# target_LED_ring_5050.net
KiCad netlist of a schematic drawn in Altium Designer
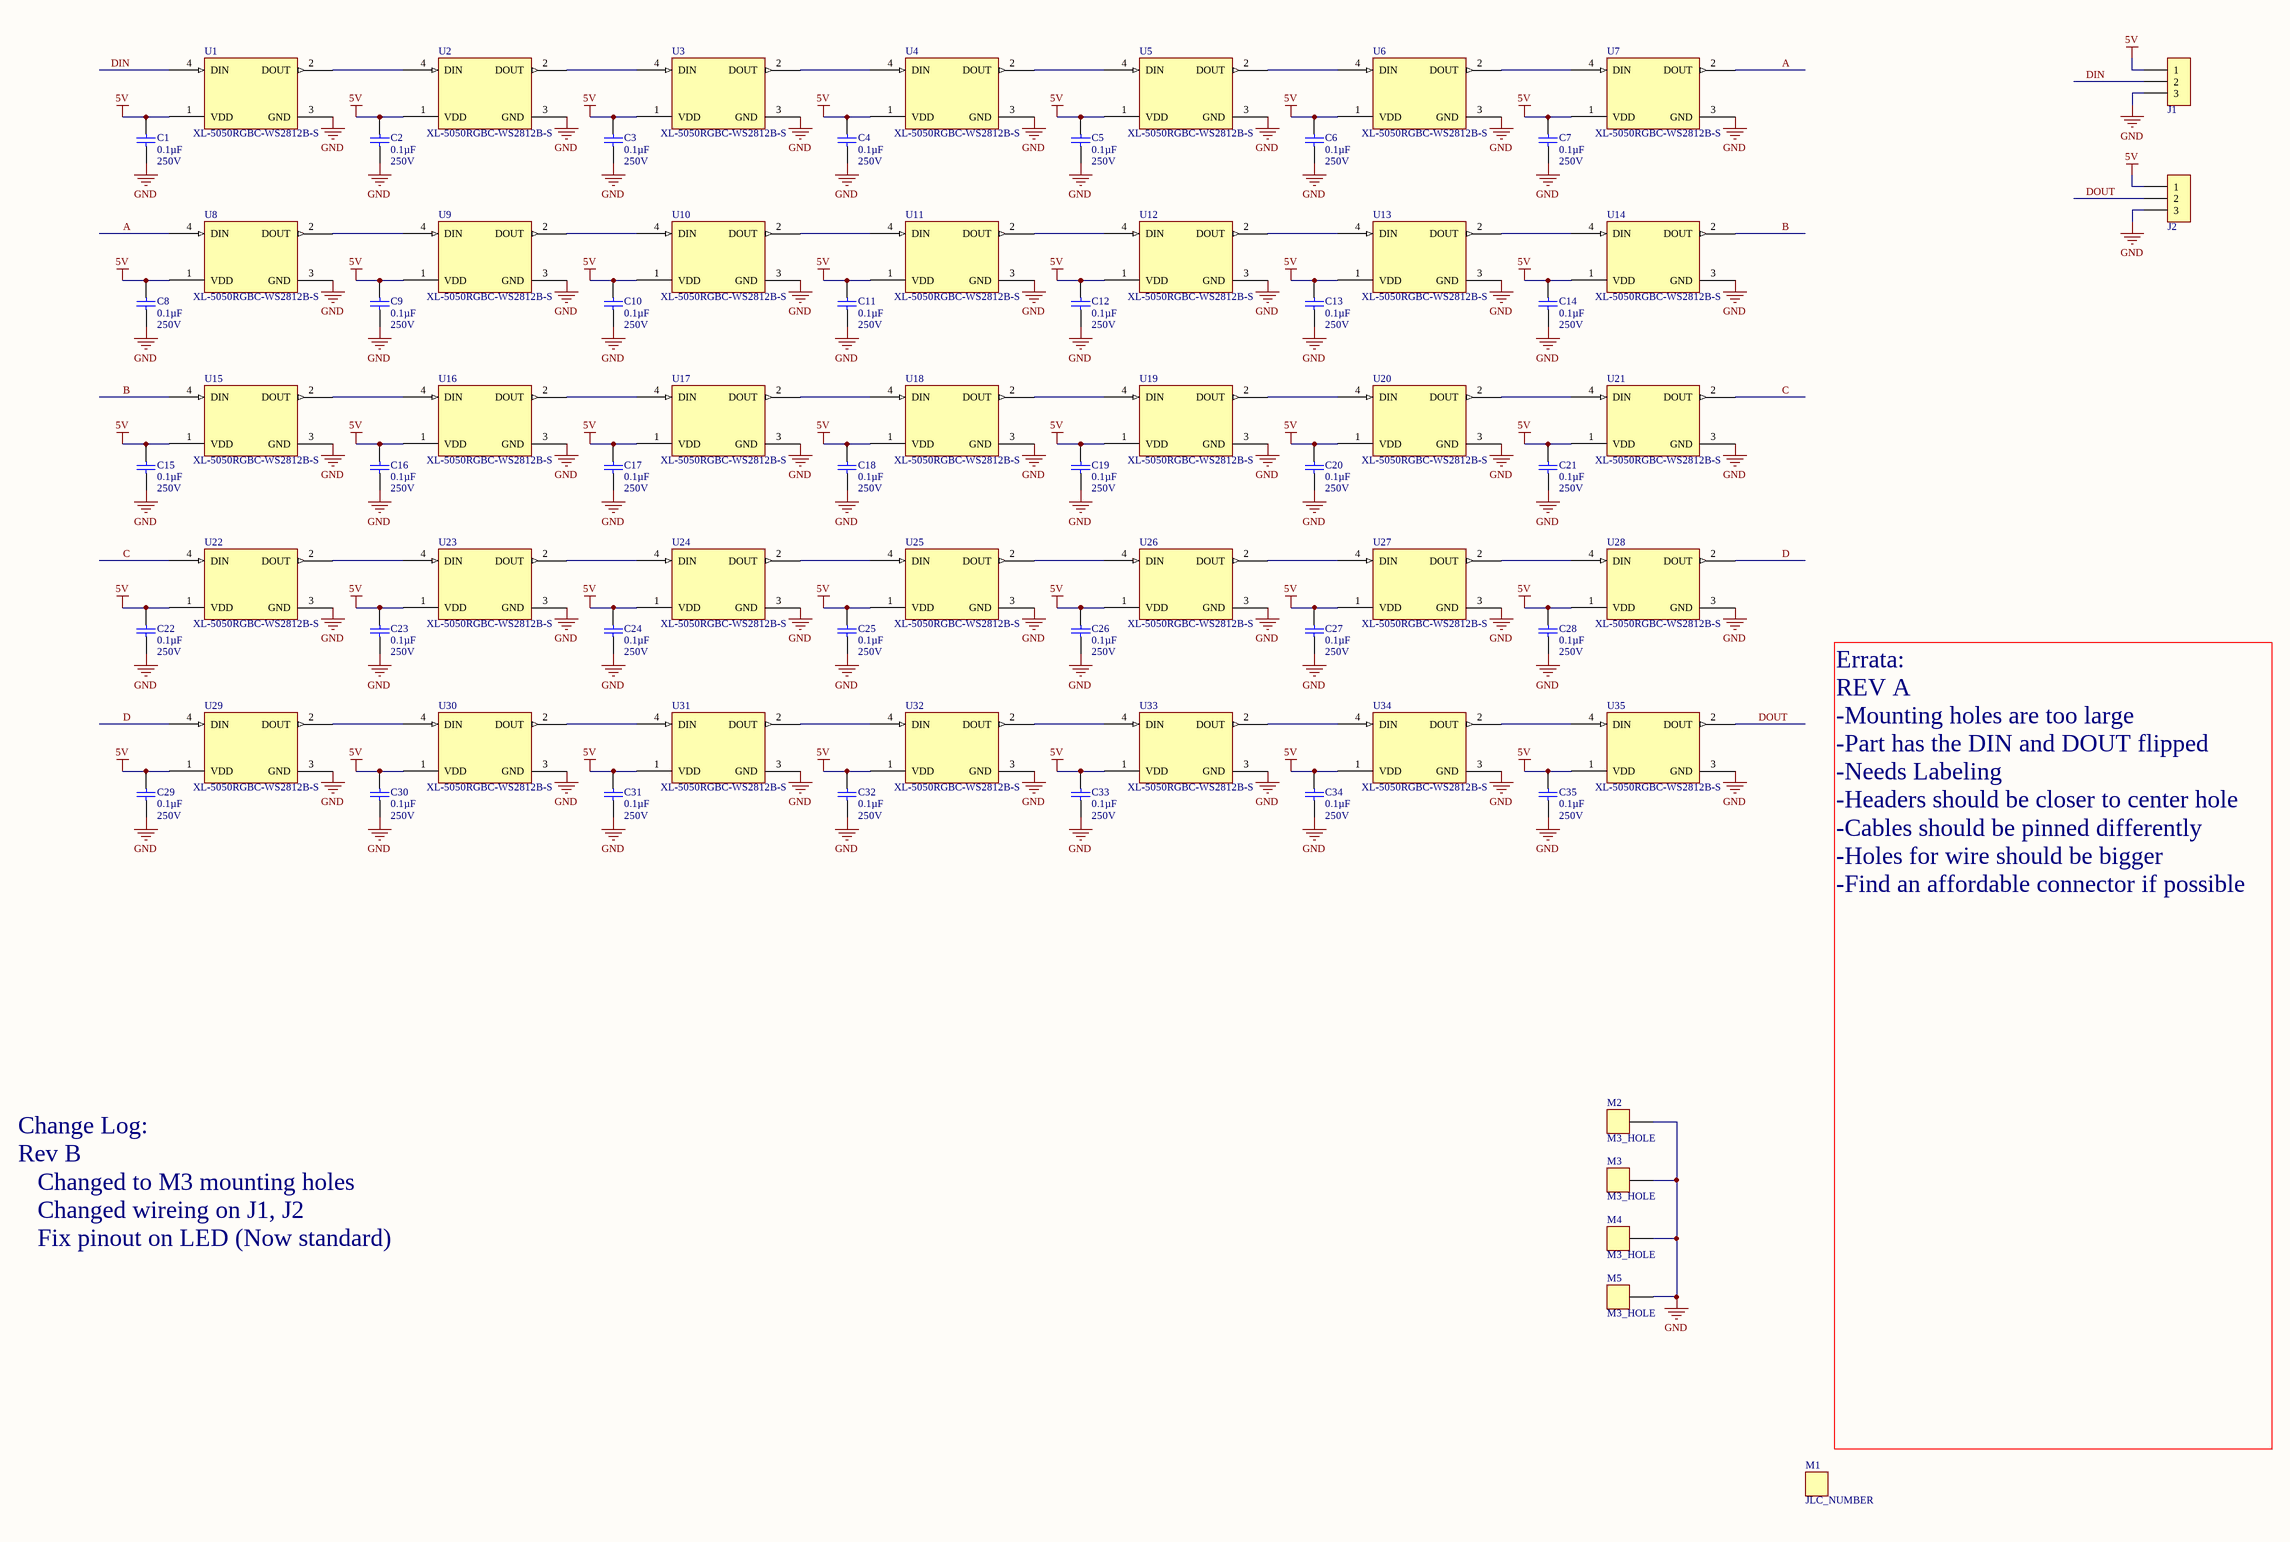
[diagram p0: target_LED_ring_5050.SchDoc]

(export (version "E")
  (design (tool "Eeschema 10.0.6"))
  (components
    (comp (ref "C1")
      (value "0.1µF")
      (footprint "Chip0805")
      (description "CAP CER 0.1UF 250V 10% X7T 0805")
      (fields
        (field (name "VOLTAGE") "250V")
        (field (name "PARTNUMBER") "C2012X7T2E104K125AA")
        (field (name "MANUFACTURER") "TDK Corporation")
      )
      (libsource (lib "Passives") (part "CAP"))
    )
    (comp (ref "C2")
      (value "0.1µF")
      (footprint "Chip0805")
      (description "CAP CER 0.1UF 250V 10% X7T 0805")
      (fields
        (field (name "VOLTAGE") "250V")
        (field (name "PARTNUMBER") "C2012X7T2E104K125AA")
        (field (name "MANUFACTURER") "TDK Corporation")
      )
      (libsource (lib "Passives") (part "CAP"))
    )
    (comp (ref "C3")
      (value "0.1µF")
      (footprint "Chip0805")
      (description "CAP CER 0.1UF 250V 10% X7T 0805")
      (fields
        (field (name "VOLTAGE") "250V")
        (field (name "PARTNUMBER") "C2012X7T2E104K125AA")
        (field (name "MANUFACTURER") "TDK Corporation")
      )
      (libsource (lib "Passives") (part "CAP"))
    )
    (comp (ref "C4")
      (value "0.1µF")
      (footprint "Chip0805")
      (description "CAP CER 0.1UF 250V 10% X7T 0805")
      (fields
        (field (name "VOLTAGE") "250V")
        (field (name "PARTNUMBER") "C2012X7T2E104K125AA")
        (field (name "MANUFACTURER") "TDK Corporation")
      )
      (libsource (lib "Passives") (part "CAP"))
    )
    (comp (ref "C5")
      (value "0.1µF")
      (footprint "Chip0805")
      (description "CAP CER 0.1UF 250V 10% X7T 0805")
      (fields
        (field (name "VOLTAGE") "250V")
        (field (name "PARTNUMBER") "C2012X7T2E104K125AA")
        (field (name "MANUFACTURER") "TDK Corporation")
      )
      (libsource (lib "Passives") (part "CAP"))
    )
    (comp (ref "C6")
      (value "0.1µF")
      (footprint "Chip0805")
      (description "CAP CER 0.1UF 250V 10% X7T 0805")
      (fields
        (field (name "VOLTAGE") "250V")
        (field (name "PARTNUMBER") "C2012X7T2E104K125AA")
        (field (name "MANUFACTURER") "TDK Corporation")
      )
      (libsource (lib "Passives") (part "CAP"))
    )
    (comp (ref "C7")
      (value "0.1µF")
      (footprint "Chip0805")
      (description "CAP CER 0.1UF 250V 10% X7T 0805")
      (fields
        (field (name "VOLTAGE") "250V")
        (field (name "PARTNUMBER") "C2012X7T2E104K125AA")
        (field (name "MANUFACTURER") "TDK Corporation")
      )
      (libsource (lib "Passives") (part "CAP"))
    )
    (comp (ref "C8")
      (value "0.1µF")
      (footprint "Chip0805")
      (description "CAP CER 0.1UF 250V 10% X7T 0805")
      (fields
        (field (name "VOLTAGE") "250V")
        (field (name "PARTNUMBER") "C2012X7T2E104K125AA")
        (field (name "MANUFACTURER") "TDK Corporation")
      )
      (libsource (lib "Passives") (part "CAP"))
    )
    (comp (ref "C9")
      (value "0.1µF")
      (footprint "Chip0805")
      (description "CAP CER 0.1UF 250V 10% X7T 0805")
      (fields
        (field (name "VOLTAGE") "250V")
        (field (name "PARTNUMBER") "C2012X7T2E104K125AA")
        (field (name "MANUFACTURER") "TDK Corporation")
      )
      (libsource (lib "Passives") (part "CAP"))
    )
    (comp (ref "C10")
      (value "0.1µF")
      (footprint "Chip0805")
      (description "CAP CER 0.1UF 250V 10% X7T 0805")
      (fields
        (field (name "VOLTAGE") "250V")
        (field (name "PARTNUMBER") "C2012X7T2E104K125AA")
        (field (name "MANUFACTURER") "TDK Corporation")
      )
      (libsource (lib "Passives") (part "CAP"))
    )
    (comp (ref "C11")
      (value "0.1µF")
      (footprint "Chip0805")
      (description "CAP CER 0.1UF 250V 10% X7T 0805")
      (fields
        (field (name "VOLTAGE") "250V")
        (field (name "PARTNUMBER") "C2012X7T2E104K125AA")
        (field (name "MANUFACTURER") "TDK Corporation")
      )
      (libsource (lib "Passives") (part "CAP"))
    )
    (comp (ref "C12")
      (value "0.1µF")
      (footprint "Chip0805")
      (description "CAP CER 0.1UF 250V 10% X7T 0805")
      (fields
        (field (name "VOLTAGE") "250V")
        (field (name "PARTNUMBER") "C2012X7T2E104K125AA")
        (field (name "MANUFACTURER") "TDK Corporation")
      )
      (libsource (lib "Passives") (part "CAP"))
    )
    (comp (ref "C13")
      (value "0.1µF")
      (footprint "Chip0805")
      (description "CAP CER 0.1UF 250V 10% X7T 0805")
      (fields
        (field (name "VOLTAGE") "250V")
        (field (name "PARTNUMBER") "C2012X7T2E104K125AA")
        (field (name "MANUFACTURER") "TDK Corporation")
      )
      (libsource (lib "Passives") (part "CAP"))
    )
    (comp (ref "C14")
      (value "0.1µF")
      (footprint "Chip0805")
      (description "CAP CER 0.1UF 250V 10% X7T 0805")
      (fields
        (field (name "VOLTAGE") "250V")
        (field (name "PARTNUMBER") "C2012X7T2E104K125AA")
        (field (name "MANUFACTURER") "TDK Corporation")
      )
      (libsource (lib "Passives") (part "CAP"))
    )
    (comp (ref "C15")
      (value "0.1µF")
      (footprint "Chip0805")
      (description "CAP CER 0.1UF 250V 10% X7T 0805")
      (fields
        (field (name "VOLTAGE") "250V")
        (field (name "PARTNUMBER") "C2012X7T2E104K125AA")
        (field (name "MANUFACTURER") "TDK Corporation")
      )
      (libsource (lib "Passives") (part "CAP"))
    )
    (comp (ref "C16")
      (value "0.1µF")
      (footprint "Chip0805")
      (description "CAP CER 0.1UF 250V 10% X7T 0805")
      (fields
        (field (name "VOLTAGE") "250V")
        (field (name "PARTNUMBER") "C2012X7T2E104K125AA")
        (field (name "MANUFACTURER") "TDK Corporation")
      )
      (libsource (lib "Passives") (part "CAP"))
    )
    (comp (ref "C17")
      (value "0.1µF")
      (footprint "Chip0805")
      (description "CAP CER 0.1UF 250V 10% X7T 0805")
      (fields
        (field (name "VOLTAGE") "250V")
        (field (name "PARTNUMBER") "C2012X7T2E104K125AA")
        (field (name "MANUFACTURER") "TDK Corporation")
      )
      (libsource (lib "Passives") (part "CAP"))
    )
    (comp (ref "C18")
      (value "0.1µF")
      (footprint "Chip0805")
      (description "CAP CER 0.1UF 250V 10% X7T 0805")
      (fields
        (field (name "VOLTAGE") "250V")
        (field (name "PARTNUMBER") "C2012X7T2E104K125AA")
        (field (name "MANUFACTURER") "TDK Corporation")
      )
      (libsource (lib "Passives") (part "CAP"))
    )
    (comp (ref "C19")
      (value "0.1µF")
      (footprint "Chip0805")
      (description "CAP CER 0.1UF 250V 10% X7T 0805")
      (fields
        (field (name "VOLTAGE") "250V")
        (field (name "PARTNUMBER") "C2012X7T2E104K125AA")
        (field (name "MANUFACTURER") "TDK Corporation")
      )
      (libsource (lib "Passives") (part "CAP"))
    )
    (comp (ref "C20")
      (value "0.1µF")
      (footprint "Chip0805")
      (description "CAP CER 0.1UF 250V 10% X7T 0805")
      (fields
        (field (name "VOLTAGE") "250V")
        (field (name "PARTNUMBER") "C2012X7T2E104K125AA")
        (field (name "MANUFACTURER") "TDK Corporation")
      )
      (libsource (lib "Passives") (part "CAP"))
    )
    (comp (ref "C21")
      (value "0.1µF")
      (footprint "Chip0805")
      (description "CAP CER 0.1UF 250V 10% X7T 0805")
      (fields
        (field (name "VOLTAGE") "250V")
        (field (name "PARTNUMBER") "C2012X7T2E104K125AA")
        (field (name "MANUFACTURER") "TDK Corporation")
      )
      (libsource (lib "Passives") (part "CAP"))
    )
    (comp (ref "C22")
      (value "0.1µF")
      (footprint "Chip0805")
      (description "CAP CER 0.1UF 250V 10% X7T 0805")
      (fields
        (field (name "VOLTAGE") "250V")
        (field (name "PARTNUMBER") "C2012X7T2E104K125AA")
        (field (name "MANUFACTURER") "TDK Corporation")
      )
      (libsource (lib "Passives") (part "CAP"))
    )
    (comp (ref "C23")
      (value "0.1µF")
      (footprint "Chip0805")
      (description "CAP CER 0.1UF 250V 10% X7T 0805")
      (fields
        (field (name "VOLTAGE") "250V")
        (field (name "PARTNUMBER") "C2012X7T2E104K125AA")
        (field (name "MANUFACTURER") "TDK Corporation")
      )
      (libsource (lib "Passives") (part "CAP"))
    )
    (comp (ref "C24")
      (value "0.1µF")
      (footprint "Chip0805")
      (description "CAP CER 0.1UF 250V 10% X7T 0805")
      (fields
        (field (name "VOLTAGE") "250V")
        (field (name "PARTNUMBER") "C2012X7T2E104K125AA")
        (field (name "MANUFACTURER") "TDK Corporation")
      )
      (libsource (lib "Passives") (part "CAP"))
    )
    (comp (ref "C25")
      (value "0.1µF")
      (footprint "Chip0805")
      (description "CAP CER 0.1UF 250V 10% X7T 0805")
      (fields
        (field (name "VOLTAGE") "250V")
        (field (name "PARTNUMBER") "C2012X7T2E104K125AA")
        (field (name "MANUFACTURER") "TDK Corporation")
      )
      (libsource (lib "Passives") (part "CAP"))
    )
    (comp (ref "C26")
      (value "0.1µF")
      (footprint "Chip0805")
      (description "CAP CER 0.1UF 250V 10% X7T 0805")
      (fields
        (field (name "VOLTAGE") "250V")
        (field (name "PARTNUMBER") "C2012X7T2E104K125AA")
        (field (name "MANUFACTURER") "TDK Corporation")
      )
      (libsource (lib "Passives") (part "CAP"))
    )
    (comp (ref "C27")
      (value "0.1µF")
      (footprint "Chip0805")
      (description "CAP CER 0.1UF 250V 10% X7T 0805")
      (fields
        (field (name "VOLTAGE") "250V")
        (field (name "PARTNUMBER") "C2012X7T2E104K125AA")
        (field (name "MANUFACTURER") "TDK Corporation")
      )
      (libsource (lib "Passives") (part "CAP"))
    )
    (comp (ref "C28")
      (value "0.1µF")
      (footprint "Chip0805")
      (description "CAP CER 0.1UF 250V 10% X7T 0805")
      (fields
        (field (name "VOLTAGE") "250V")
        (field (name "PARTNUMBER") "C2012X7T2E104K125AA")
        (field (name "MANUFACTURER") "TDK Corporation")
      )
      (libsource (lib "Passives") (part "CAP"))
    )
    (comp (ref "C29")
      (value "0.1µF")
      (footprint "Chip0805")
      (description "CAP CER 0.1UF 250V 10% X7T 0805")
      (fields
        (field (name "VOLTAGE") "250V")
        (field (name "PARTNUMBER") "C2012X7T2E104K125AA")
        (field (name "MANUFACTURER") "TDK Corporation")
      )
      (libsource (lib "Passives") (part "CAP"))
    )
    (comp (ref "C30")
      (value "0.1µF")
      (footprint "Chip0805")
      (description "CAP CER 0.1UF 250V 10% X7T 0805")
      (fields
        (field (name "VOLTAGE") "250V")
        (field (name "PARTNUMBER") "C2012X7T2E104K125AA")
        (field (name "MANUFACTURER") "TDK Corporation")
      )
      (libsource (lib "Passives") (part "CAP"))
    )
    (comp (ref "C31")
      (value "0.1µF")
      (footprint "Chip0805")
      (description "CAP CER 0.1UF 250V 10% X7T 0805")
      (fields
        (field (name "VOLTAGE") "250V")
        (field (name "PARTNUMBER") "C2012X7T2E104K125AA")
        (field (name "MANUFACTURER") "TDK Corporation")
      )
      (libsource (lib "Passives") (part "CAP"))
    )
    (comp (ref "C32")
      (value "0.1µF")
      (footprint "Chip0805")
      (description "CAP CER 0.1UF 250V 10% X7T 0805")
      (fields
        (field (name "VOLTAGE") "250V")
        (field (name "PARTNUMBER") "C2012X7T2E104K125AA")
        (field (name "MANUFACTURER") "TDK Corporation")
      )
      (libsource (lib "Passives") (part "CAP"))
    )
    (comp (ref "C33")
      (value "0.1µF")
      (footprint "Chip0805")
      (description "CAP CER 0.1UF 250V 10% X7T 0805")
      (fields
        (field (name "VOLTAGE") "250V")
        (field (name "PARTNUMBER") "C2012X7T2E104K125AA")
        (field (name "MANUFACTURER") "TDK Corporation")
      )
      (libsource (lib "Passives") (part "CAP"))
    )
    (comp (ref "C34")
      (value "0.1µF")
      (footprint "Chip0805")
      (description "CAP CER 0.1UF 250V 10% X7T 0805")
      (fields
        (field (name "VOLTAGE") "250V")
        (field (name "PARTNUMBER") "C2012X7T2E104K125AA")
        (field (name "MANUFACTURER") "TDK Corporation")
      )
      (libsource (lib "Passives") (part "CAP"))
    )
    (comp (ref "C35")
      (value "0.1µF")
      (footprint "Chip0805")
      (description "CAP CER 0.1UF 250V 10% X7T 0805")
      (fields
        (field (name "VOLTAGE") "250V")
        (field (name "PARTNUMBER") "C2012X7T2E104K125AA")
        (field (name "MANUFACTURER") "TDK Corporation")
      )
      (libsource (lib "Passives") (part "CAP"))
    )
    (comp (ref "J1")
      (value "3-644456-3")
      (footprint "TE_3-644456-3")
      (description "CONN HEADER VERT 3POS .100 TIN")
      (fields (field (name "MANUFACTURER") "TE Connectivity"))
      (libsource (lib "Connectors") (part "HEADER_1x3"))
    )
    (comp (ref "J2")
      (value "3-644456-3")
      (footprint "TE_3-644456-3")
      (description "CONN HEADER VERT 3POS .100 TIN")
      (fields (field (name "MANUFACTURER") "TE Connectivity"))
      (libsource (lib "Connectors") (part "HEADER_1x3"))
    )
    (comp (ref "M1")
      (value "JLC_NUMBER")
      (footprint "JLC_NUMBER")
      (description "JLC Order Number Location")
      (libsource (lib "Mechanical") (part "MECH_NO_BOM"))
    )
    (comp (ref "M2")
      (value "M3_HOLE")
      (footprint "M3_HOLE")
      (libsource (lib "Mechanical") (part "MECH_1PIN_NO_BOM"))
    )
    (comp (ref "M3")
      (value "M3_HOLE")
      (footprint "M3_HOLE")
      (libsource (lib "Mechanical") (part "MECH_1PIN_NO_BOM"))
    )
    (comp (ref "M4")
      (value "M3_HOLE")
      (footprint "M3_HOLE")
      (libsource (lib "Mechanical") (part "MECH_1PIN_NO_BOM"))
    )
    (comp (ref "M5")
      (value "M3_HOLE")
      (footprint "M3_HOLE")
      (libsource (lib "Mechanical") (part "MECH_1PIN_NO_BOM"))
    )
    (comp (ref "U1")
      (value "XL-5050RGBC-WS2812B-S")
      (footprint "XINGLIGHT_XL-5050RGBC-WS2812B-S")
      (description "Addressable RGB LED")
      (fields (field (name "MANUFACTURER") "XINGLIGHT"))
      (libsource (lib "Optoelectronics") (part "XINGLIGHT_XL-5050RGBC-WS2812B-S"))
    )
    (comp (ref "U2")
      (value "XL-5050RGBC-WS2812B-S")
      (footprint "XINGLIGHT_XL-5050RGBC-WS2812B-S")
      (description "Addressable RGB LED")
      (fields (field (name "MANUFACTURER") "XINGLIGHT"))
      (libsource (lib "Optoelectronics") (part "XINGLIGHT_XL-5050RGBC-WS2812B-S"))
    )
    (comp (ref "U3")
      (value "XL-5050RGBC-WS2812B-S")
      (footprint "XINGLIGHT_XL-5050RGBC-WS2812B-S")
      (description "Addressable RGB LED")
      (fields (field (name "MANUFACTURER") "XINGLIGHT"))
      (libsource (lib "Optoelectronics") (part "XINGLIGHT_XL-5050RGBC-WS2812B-S"))
    )
    (comp (ref "U4")
      (value "XL-5050RGBC-WS2812B-S")
      (footprint "XINGLIGHT_XL-5050RGBC-WS2812B-S")
      (description "Addressable RGB LED")
      (fields (field (name "MANUFACTURER") "XINGLIGHT"))
      (libsource (lib "Optoelectronics") (part "XINGLIGHT_XL-5050RGBC-WS2812B-S"))
    )
    (comp (ref "U5")
      (value "XL-5050RGBC-WS2812B-S")
      (footprint "XINGLIGHT_XL-5050RGBC-WS2812B-S")
      (description "Addressable RGB LED")
      (fields (field (name "MANUFACTURER") "XINGLIGHT"))
      (libsource (lib "Optoelectronics") (part "XINGLIGHT_XL-5050RGBC-WS2812B-S"))
    )
    (comp (ref "U6")
      (value "XL-5050RGBC-WS2812B-S")
      (footprint "XINGLIGHT_XL-5050RGBC-WS2812B-S")
      (description "Addressable RGB LED")
      (fields (field (name "MANUFACTURER") "XINGLIGHT"))
      (libsource (lib "Optoelectronics") (part "XINGLIGHT_XL-5050RGBC-WS2812B-S"))
    )
    (comp (ref "U7")
      (value "XL-5050RGBC-WS2812B-S")
      (footprint "XINGLIGHT_XL-5050RGBC-WS2812B-S")
      (description "Addressable RGB LED")
      (fields (field (name "MANUFACTURER") "XINGLIGHT"))
      (libsource (lib "Optoelectronics") (part "XINGLIGHT_XL-5050RGBC-WS2812B-S"))
    )
    (comp (ref "U8")
      (value "XL-5050RGBC-WS2812B-S")
      (footprint "XINGLIGHT_XL-5050RGBC-WS2812B-S")
      (description "Addressable RGB LED")
      (fields (field (name "MANUFACTURER") "XINGLIGHT"))
      (libsource (lib "Optoelectronics") (part "XINGLIGHT_XL-5050RGBC-WS2812B-S"))
    )
    (comp (ref "U9")
      (value "XL-5050RGBC-WS2812B-S")
      (footprint "XINGLIGHT_XL-5050RGBC-WS2812B-S")
      (description "Addressable RGB LED")
      (fields (field (name "MANUFACTURER") "XINGLIGHT"))
      (libsource (lib "Optoelectronics") (part "XINGLIGHT_XL-5050RGBC-WS2812B-S"))
    )
    (comp (ref "U10")
      (value "XL-5050RGBC-WS2812B-S")
      (footprint "XINGLIGHT_XL-5050RGBC-WS2812B-S")
      (description "Addressable RGB LED")
      (fields (field (name "MANUFACTURER") "XINGLIGHT"))
      (libsource (lib "Optoelectronics") (part "XINGLIGHT_XL-5050RGBC-WS2812B-S"))
    )
    (comp (ref "U11")
      (value "XL-5050RGBC-WS2812B-S")
      (footprint "XINGLIGHT_XL-5050RGBC-WS2812B-S")
      (description "Addressable RGB LED")
      (fields (field (name "MANUFACTURER") "XINGLIGHT"))
      (libsource (lib "Optoelectronics") (part "XINGLIGHT_XL-5050RGBC-WS2812B-S"))
    )
    (comp (ref "U12")
      (value "XL-5050RGBC-WS2812B-S")
      (footprint "XINGLIGHT_XL-5050RGBC-WS2812B-S")
      (description "Addressable RGB LED")
      (fields (field (name "MANUFACTURER") "XINGLIGHT"))
      (libsource (lib "Optoelectronics") (part "XINGLIGHT_XL-5050RGBC-WS2812B-S"))
    )
    (comp (ref "U13")
      (value "XL-5050RGBC-WS2812B-S")
      (footprint "XINGLIGHT_XL-5050RGBC-WS2812B-S")
      (description "Addressable RGB LED")
      (fields (field (name "MANUFACTURER") "XINGLIGHT"))
      (libsource (lib "Optoelectronics") (part "XINGLIGHT_XL-5050RGBC-WS2812B-S"))
    )
    (comp (ref "U14")
      (value "XL-5050RGBC-WS2812B-S")
      (footprint "XINGLIGHT_XL-5050RGBC-WS2812B-S")
      (description "Addressable RGB LED")
      (fields (field (name "MANUFACTURER") "XINGLIGHT"))
      (libsource (lib "Optoelectronics") (part "XINGLIGHT_XL-5050RGBC-WS2812B-S"))
    )
    (comp (ref "U15")
      (value "XL-5050RGBC-WS2812B-S")
      (footprint "XINGLIGHT_XL-5050RGBC-WS2812B-S")
      (description "Addressable RGB LED")
      (fields (field (name "MANUFACTURER") "XINGLIGHT"))
      (libsource (lib "Optoelectronics") (part "XINGLIGHT_XL-5050RGBC-WS2812B-S"))
    )
    (comp (ref "U16")
      (value "XL-5050RGBC-WS2812B-S")
      (footprint "XINGLIGHT_XL-5050RGBC-WS2812B-S")
      (description "Addressable RGB LED")
      (fields (field (name "MANUFACTURER") "XINGLIGHT"))
      (libsource (lib "Optoelectronics") (part "XINGLIGHT_XL-5050RGBC-WS2812B-S"))
    )
    (comp (ref "U17")
      (value "XL-5050RGBC-WS2812B-S")
      (footprint "XINGLIGHT_XL-5050RGBC-WS2812B-S")
      (description "Addressable RGB LED")
      (fields (field (name "MANUFACTURER") "XINGLIGHT"))
      (libsource (lib "Optoelectronics") (part "XINGLIGHT_XL-5050RGBC-WS2812B-S"))
    )
    (comp (ref "U18")
      (value "XL-5050RGBC-WS2812B-S")
      (footprint "XINGLIGHT_XL-5050RGBC-WS2812B-S")
      (description "Addressable RGB LED")
      (fields (field (name "MANUFACTURER") "XINGLIGHT"))
      (libsource (lib "Optoelectronics") (part "XINGLIGHT_XL-5050RGBC-WS2812B-S"))
    )
    (comp (ref "U19")
      (value "XL-5050RGBC-WS2812B-S")
      (footprint "XINGLIGHT_XL-5050RGBC-WS2812B-S")
      (description "Addressable RGB LED")
      (fields (field (name "MANUFACTURER") "XINGLIGHT"))
      (libsource (lib "Optoelectronics") (part "XINGLIGHT_XL-5050RGBC-WS2812B-S"))
    )
    (comp (ref "U20")
      (value "XL-5050RGBC-WS2812B-S")
      (footprint "XINGLIGHT_XL-5050RGBC-WS2812B-S")
      (description "Addressable RGB LED")
      (fields (field (name "MANUFACTURER") "XINGLIGHT"))
      (libsource (lib "Optoelectronics") (part "XINGLIGHT_XL-5050RGBC-WS2812B-S"))
    )
    (comp (ref "U21")
      (value "XL-5050RGBC-WS2812B-S")
      (footprint "XINGLIGHT_XL-5050RGBC-WS2812B-S")
      (description "Addressable RGB LED")
      (fields (field (name "MANUFACTURER") "XINGLIGHT"))
      (libsource (lib "Optoelectronics") (part "XINGLIGHT_XL-5050RGBC-WS2812B-S"))
    )
    (comp (ref "U22")
      (value "XL-5050RGBC-WS2812B-S")
      (footprint "XINGLIGHT_XL-5050RGBC-WS2812B-S")
      (description "Addressable RGB LED")
      (fields (field (name "MANUFACTURER") "XINGLIGHT"))
      (libsource (lib "Optoelectronics") (part "XINGLIGHT_XL-5050RGBC-WS2812B-S"))
    )
    (comp (ref "U23")
      (value "XL-5050RGBC-WS2812B-S")
      (footprint "XINGLIGHT_XL-5050RGBC-WS2812B-S")
      (description "Addressable RGB LED")
      (fields (field (name "MANUFACTURER") "XINGLIGHT"))
      (libsource (lib "Optoelectronics") (part "XINGLIGHT_XL-5050RGBC-WS2812B-S"))
    )
    (comp (ref "U24")
      (value "XL-5050RGBC-WS2812B-S")
      (footprint "XINGLIGHT_XL-5050RGBC-WS2812B-S")
      (description "Addressable RGB LED")
      (fields (field (name "MANUFACTURER") "XINGLIGHT"))
      (libsource (lib "Optoelectronics") (part "XINGLIGHT_XL-5050RGBC-WS2812B-S"))
    )
    (comp (ref "U25")
      (value "XL-5050RGBC-WS2812B-S")
      (footprint "XINGLIGHT_XL-5050RGBC-WS2812B-S")
      (description "Addressable RGB LED")
      (fields (field (name "MANUFACTURER") "XINGLIGHT"))
      (libsource (lib "Optoelectronics") (part "XINGLIGHT_XL-5050RGBC-WS2812B-S"))
    )
    (comp (ref "U26")
      (value "XL-5050RGBC-WS2812B-S")
      (footprint "XINGLIGHT_XL-5050RGBC-WS2812B-S")
      (description "Addressable RGB LED")
      (fields (field (name "MANUFACTURER") "XINGLIGHT"))
      (libsource (lib "Optoelectronics") (part "XINGLIGHT_XL-5050RGBC-WS2812B-S"))
    )
    (comp (ref "U27")
      (value "XL-5050RGBC-WS2812B-S")
      (footprint "XINGLIGHT_XL-5050RGBC-WS2812B-S")
      (description "Addressable RGB LED")
      (fields (field (name "MANUFACTURER") "XINGLIGHT"))
      (libsource (lib "Optoelectronics") (part "XINGLIGHT_XL-5050RGBC-WS2812B-S"))
    )
    (comp (ref "U28")
      (value "XL-5050RGBC-WS2812B-S")
      (footprint "XINGLIGHT_XL-5050RGBC-WS2812B-S")
      (description "Addressable RGB LED")
      (fields (field (name "MANUFACTURER") "XINGLIGHT"))
      (libsource (lib "Optoelectronics") (part "XINGLIGHT_XL-5050RGBC-WS2812B-S"))
    )
    (comp (ref "U29")
      (value "XL-5050RGBC-WS2812B-S")
      (footprint "XINGLIGHT_XL-5050RGBC-WS2812B-S")
      (description "Addressable RGB LED")
      (fields (field (name "MANUFACTURER") "XINGLIGHT"))
      (libsource (lib "Optoelectronics") (part "XINGLIGHT_XL-5050RGBC-WS2812B-S"))
    )
    (comp (ref "U30")
      (value "XL-5050RGBC-WS2812B-S")
      (footprint "XINGLIGHT_XL-5050RGBC-WS2812B-S")
      (description "Addressable RGB LED")
      (fields (field (name "MANUFACTURER") "XINGLIGHT"))
      (libsource (lib "Optoelectronics") (part "XINGLIGHT_XL-5050RGBC-WS2812B-S"))
    )
    (comp (ref "U31")
      (value "XL-5050RGBC-WS2812B-S")
      (footprint "XINGLIGHT_XL-5050RGBC-WS2812B-S")
      (description "Addressable RGB LED")
      (fields (field (name "MANUFACTURER") "XINGLIGHT"))
      (libsource (lib "Optoelectronics") (part "XINGLIGHT_XL-5050RGBC-WS2812B-S"))
    )
    (comp (ref "U32")
      (value "XL-5050RGBC-WS2812B-S")
      (footprint "XINGLIGHT_XL-5050RGBC-WS2812B-S")
      (description "Addressable RGB LED")
      (fields (field (name "MANUFACTURER") "XINGLIGHT"))
      (libsource (lib "Optoelectronics") (part "XINGLIGHT_XL-5050RGBC-WS2812B-S"))
    )
    (comp (ref "U33")
      (value "XL-5050RGBC-WS2812B-S")
      (footprint "XINGLIGHT_XL-5050RGBC-WS2812B-S")
      (description "Addressable RGB LED")
      (fields (field (name "MANUFACTURER") "XINGLIGHT"))
      (libsource (lib "Optoelectronics") (part "XINGLIGHT_XL-5050RGBC-WS2812B-S"))
    )
    (comp (ref "U34")
      (value "XL-5050RGBC-WS2812B-S")
      (footprint "XINGLIGHT_XL-5050RGBC-WS2812B-S")
      (description "Addressable RGB LED")
      (fields (field (name "MANUFACTURER") "XINGLIGHT"))
      (libsource (lib "Optoelectronics") (part "XINGLIGHT_XL-5050RGBC-WS2812B-S"))
    )
    (comp (ref "U35")
      (value "XL-5050RGBC-WS2812B-S")
      (footprint "XINGLIGHT_XL-5050RGBC-WS2812B-S")
      (description "Addressable RGB LED")
      (fields (field (name "MANUFACTURER") "XINGLIGHT"))
      (libsource (lib "Optoelectronics") (part "XINGLIGHT_XL-5050RGBC-WS2812B-S"))
    )
  )
  (nets
    (net (code "1") (name "/A") (class "Default")
      (node (ref "U7") (pin "2") (pinfunction "DOUT_2") (pintype "output"))
      (node (ref "U8") (pin "4") (pinfunction "DIN_4") (pintype "input"))
    )
    (net (code "2") (name "/B") (class "Default")
      (node (ref "U14") (pin "2") (pinfunction "DOUT_2") (pintype "output"))
      (node (ref "U15") (pin "4") (pinfunction "DIN_4") (pintype "input"))
    )
    (net (code "3") (name "/C") (class "Default")
      (node (ref "U21") (pin "2") (pinfunction "DOUT_2") (pintype "output"))
      (node (ref "U22") (pin "4") (pinfunction "DIN_4") (pintype "input"))
    )
    (net (code "4") (name "/D") (class "Default")
      (node (ref "U28") (pin "2") (pinfunction "DOUT_2") (pintype "output"))
      (node (ref "U29") (pin "4") (pinfunction "DIN_4") (pintype "input"))
    )
    (net (code "5") (name "/DIN") (class "Default")
      (node (ref "J1") (pin "2") (pinfunction "2_2") (pintype "passive"))
      (node (ref "U1") (pin "4") (pinfunction "DIN_4") (pintype "input"))
    )
    (net (code "6") (name "/DOUT") (class "Default")
      (node (ref "J2") (pin "2") (pinfunction "2_2") (pintype "passive"))
      (node (ref "U35") (pin "2") (pinfunction "DOUT_2") (pintype "output"))
    )
    (net (code "7") (name "5V") (class "Default")
      (node (ref "C1") (pin "2") (pinfunction "2_2") (pintype "passive"))
      (node (ref "C10") (pin "2") (pinfunction "2_2") (pintype "passive"))
      (node (ref "C11") (pin "2") (pinfunction "2_2") (pintype "passive"))
      (node (ref "C12") (pin "2") (pinfunction "2_2") (pintype "passive"))
      (node (ref "C13") (pin "2") (pinfunction "2_2") (pintype "passive"))
      (node (ref "C14") (pin "2") (pinfunction "2_2") (pintype "passive"))
      (node (ref "C15") (pin "2") (pinfunction "2_2") (pintype "passive"))
      (node (ref "C16") (pin "2") (pinfunction "2_2") (pintype "passive"))
      (node (ref "C17") (pin "2") (pinfunction "2_2") (pintype "passive"))
      (node (ref "C18") (pin "2") (pinfunction "2_2") (pintype "passive"))
      (node (ref "C19") (pin "2") (pinfunction "2_2") (pintype "passive"))
      (node (ref "C2") (pin "2") (pinfunction "2_2") (pintype "passive"))
      (node (ref "C20") (pin "2") (pinfunction "2_2") (pintype "passive"))
      (node (ref "C21") (pin "2") (pinfunction "2_2") (pintype "passive"))
      (node (ref "C22") (pin "2") (pinfunction "2_2") (pintype "passive"))
      (node (ref "C23") (pin "2") (pinfunction "2_2") (pintype "passive"))
      (node (ref "C24") (pin "2") (pinfunction "2_2") (pintype "passive"))
      (node (ref "C25") (pin "2") (pinfunction "2_2") (pintype "passive"))
      (node (ref "C26") (pin "2") (pinfunction "2_2") (pintype "passive"))
      (node (ref "C27") (pin "2") (pinfunction "2_2") (pintype "passive"))
      (node (ref "C28") (pin "2") (pinfunction "2_2") (pintype "passive"))
      (node (ref "C29") (pin "2") (pinfunction "2_2") (pintype "passive"))
      (node (ref "C3") (pin "2") (pinfunction "2_2") (pintype "passive"))
      (node (ref "C30") (pin "2") (pinfunction "2_2") (pintype "passive"))
      (node (ref "C31") (pin "2") (pinfunction "2_2") (pintype "passive"))
      (node (ref "C32") (pin "2") (pinfunction "2_2") (pintype "passive"))
      (node (ref "C33") (pin "2") (pinfunction "2_2") (pintype "passive"))
      (node (ref "C34") (pin "2") (pinfunction "2_2") (pintype "passive"))
      (node (ref "C35") (pin "2") (pinfunction "2_2") (pintype "passive"))
      (node (ref "C4") (pin "2") (pinfunction "2_2") (pintype "passive"))
      (node (ref "C5") (pin "2") (pinfunction "2_2") (pintype "passive"))
      (node (ref "C6") (pin "2") (pinfunction "2_2") (pintype "passive"))
      (node (ref "C7") (pin "2") (pinfunction "2_2") (pintype "passive"))
      (node (ref "C8") (pin "2") (pinfunction "2_2") (pintype "passive"))
      (node (ref "C9") (pin "2") (pinfunction "2_2") (pintype "passive"))
      (node (ref "J1") (pin "1") (pinfunction "1_1") (pintype "passive"))
      (node (ref "J2") (pin "1") (pinfunction "1_1") (pintype "passive"))
      (node (ref "U1") (pin "1") (pinfunction "VDD_1") (pintype "passive"))
      (node (ref "U10") (pin "1") (pinfunction "VDD_1") (pintype "passive"))
      (node (ref "U11") (pin "1") (pinfunction "VDD_1") (pintype "passive"))
      (node (ref "U12") (pin "1") (pinfunction "VDD_1") (pintype "passive"))
      (node (ref "U13") (pin "1") (pinfunction "VDD_1") (pintype "passive"))
      (node (ref "U14") (pin "1") (pinfunction "VDD_1") (pintype "passive"))
      (node (ref "U15") (pin "1") (pinfunction "VDD_1") (pintype "passive"))
      (node (ref "U16") (pin "1") (pinfunction "VDD_1") (pintype "passive"))
      (node (ref "U17") (pin "1") (pinfunction "VDD_1") (pintype "passive"))
      (node (ref "U18") (pin "1") (pinfunction "VDD_1") (pintype "passive"))
      (node (ref "U19") (pin "1") (pinfunction "VDD_1") (pintype "passive"))
      (node (ref "U2") (pin "1") (pinfunction "VDD_1") (pintype "passive"))
      (node (ref "U20") (pin "1") (pinfunction "VDD_1") (pintype "passive"))
      (node (ref "U21") (pin "1") (pinfunction "VDD_1") (pintype "passive"))
      (node (ref "U22") (pin "1") (pinfunction "VDD_1") (pintype "passive"))
      (node (ref "U23") (pin "1") (pinfunction "VDD_1") (pintype "passive"))
      (node (ref "U24") (pin "1") (pinfunction "VDD_1") (pintype "passive"))
      (node (ref "U25") (pin "1") (pinfunction "VDD_1") (pintype "passive"))
      (node (ref "U26") (pin "1") (pinfunction "VDD_1") (pintype "passive"))
      (node (ref "U27") (pin "1") (pinfunction "VDD_1") (pintype "passive"))
      (node (ref "U28") (pin "1") (pinfunction "VDD_1") (pintype "passive"))
      (node (ref "U29") (pin "1") (pinfunction "VDD_1") (pintype "passive"))
      (node (ref "U3") (pin "1") (pinfunction "VDD_1") (pintype "passive"))
      (node (ref "U30") (pin "1") (pinfunction "VDD_1") (pintype "passive"))
      (node (ref "U31") (pin "1") (pinfunction "VDD_1") (pintype "passive"))
      (node (ref "U32") (pin "1") (pinfunction "VDD_1") (pintype "passive"))
      (node (ref "U33") (pin "1") (pinfunction "VDD_1") (pintype "passive"))
      (node (ref "U34") (pin "1") (pinfunction "VDD_1") (pintype "passive"))
      (node (ref "U35") (pin "1") (pinfunction "VDD_1") (pintype "passive"))
      (node (ref "U4") (pin "1") (pinfunction "VDD_1") (pintype "passive"))
      (node (ref "U5") (pin "1") (pinfunction "VDD_1") (pintype "passive"))
      (node (ref "U6") (pin "1") (pinfunction "VDD_1") (pintype "passive"))
      (node (ref "U7") (pin "1") (pinfunction "VDD_1") (pintype "passive"))
      (node (ref "U8") (pin "1") (pinfunction "VDD_1") (pintype "passive"))
      (node (ref "U9") (pin "1") (pinfunction "VDD_1") (pintype "passive"))
    )
    (net (code "8") (name "GND") (class "Default")
      (node (ref "C1") (pin "1") (pinfunction "1_1") (pintype "passive"))
      (node (ref "C10") (pin "1") (pinfunction "1_1") (pintype "passive"))
      (node (ref "C11") (pin "1") (pinfunction "1_1") (pintype "passive"))
      (node (ref "C12") (pin "1") (pinfunction "1_1") (pintype "passive"))
      (node (ref "C13") (pin "1") (pinfunction "1_1") (pintype "passive"))
      (node (ref "C14") (pin "1") (pinfunction "1_1") (pintype "passive"))
      (node (ref "C15") (pin "1") (pinfunction "1_1") (pintype "passive"))
      (node (ref "C16") (pin "1") (pinfunction "1_1") (pintype "passive"))
      (node (ref "C17") (pin "1") (pinfunction "1_1") (pintype "passive"))
      (node (ref "C18") (pin "1") (pinfunction "1_1") (pintype "passive"))
      (node (ref "C19") (pin "1") (pinfunction "1_1") (pintype "passive"))
      (node (ref "C2") (pin "1") (pinfunction "1_1") (pintype "passive"))
      (node (ref "C20") (pin "1") (pinfunction "1_1") (pintype "passive"))
      (node (ref "C21") (pin "1") (pinfunction "1_1") (pintype "passive"))
      (node (ref "C22") (pin "1") (pinfunction "1_1") (pintype "passive"))
      (node (ref "C23") (pin "1") (pinfunction "1_1") (pintype "passive"))
      (node (ref "C24") (pin "1") (pinfunction "1_1") (pintype "passive"))
      (node (ref "C25") (pin "1") (pinfunction "1_1") (pintype "passive"))
      (node (ref "C26") (pin "1") (pinfunction "1_1") (pintype "passive"))
      (node (ref "C27") (pin "1") (pinfunction "1_1") (pintype "passive"))
      (node (ref "C28") (pin "1") (pinfunction "1_1") (pintype "passive"))
      (node (ref "C29") (pin "1") (pinfunction "1_1") (pintype "passive"))
      (node (ref "C3") (pin "1") (pinfunction "1_1") (pintype "passive"))
      (node (ref "C30") (pin "1") (pinfunction "1_1") (pintype "passive"))
      (node (ref "C31") (pin "1") (pinfunction "1_1") (pintype "passive"))
      (node (ref "C32") (pin "1") (pinfunction "1_1") (pintype "passive"))
      (node (ref "C33") (pin "1") (pinfunction "1_1") (pintype "passive"))
      (node (ref "C34") (pin "1") (pinfunction "1_1") (pintype "passive"))
      (node (ref "C35") (pin "1") (pinfunction "1_1") (pintype "passive"))
      (node (ref "C4") (pin "1") (pinfunction "1_1") (pintype "passive"))
      (node (ref "C5") (pin "1") (pinfunction "1_1") (pintype "passive"))
      (node (ref "C6") (pin "1") (pinfunction "1_1") (pintype "passive"))
      (node (ref "C7") (pin "1") (pinfunction "1_1") (pintype "passive"))
      (node (ref "C8") (pin "1") (pinfunction "1_1") (pintype "passive"))
      (node (ref "C9") (pin "1") (pinfunction "1_1") (pintype "passive"))
      (node (ref "J1") (pin "3") (pinfunction "3_3") (pintype "passive"))
      (node (ref "J2") (pin "3") (pinfunction "3_3") (pintype "passive"))
      (node (ref "M2") (pin "1") (pinfunction "1_1") (pintype "passive"))
      (node (ref "M3") (pin "1") (pinfunction "1_1") (pintype "passive"))
      (node (ref "M4") (pin "1") (pinfunction "1_1") (pintype "passive"))
      (node (ref "M5") (pin "1") (pinfunction "1_1") (pintype "passive"))
      (node (ref "U1") (pin "3") (pinfunction "GND_3") (pintype "passive"))
      (node (ref "U10") (pin "3") (pinfunction "GND_3") (pintype "passive"))
      (node (ref "U11") (pin "3") (pinfunction "GND_3") (pintype "passive"))
      (node (ref "U12") (pin "3") (pinfunction "GND_3") (pintype "passive"))
      (node (ref "U13") (pin "3") (pinfunction "GND_3") (pintype "passive"))
      (node (ref "U14") (pin "3") (pinfunction "GND_3") (pintype "passive"))
      (node (ref "U15") (pin "3") (pinfunction "GND_3") (pintype "passive"))
      (node (ref "U16") (pin "3") (pinfunction "GND_3") (pintype "passive"))
      (node (ref "U17") (pin "3") (pinfunction "GND_3") (pintype "passive"))
      (node (ref "U18") (pin "3") (pinfunction "GND_3") (pintype "passive"))
      (node (ref "U19") (pin "3") (pinfunction "GND_3") (pintype "passive"))
      (node (ref "U2") (pin "3") (pinfunction "GND_3") (pintype "passive"))
      (node (ref "U20") (pin "3") (pinfunction "GND_3") (pintype "passive"))
      (node (ref "U21") (pin "3") (pinfunction "GND_3") (pintype "passive"))
      (node (ref "U22") (pin "3") (pinfunction "GND_3") (pintype "passive"))
      (node (ref "U23") (pin "3") (pinfunction "GND_3") (pintype "passive"))
      (node (ref "U24") (pin "3") (pinfunction "GND_3") (pintype "passive"))
      (node (ref "U25") (pin "3") (pinfunction "GND_3") (pintype "passive"))
      (node (ref "U26") (pin "3") (pinfunction "GND_3") (pintype "passive"))
      (node (ref "U27") (pin "3") (pinfunction "GND_3") (pintype "passive"))
      (node (ref "U28") (pin "3") (pinfunction "GND_3") (pintype "passive"))
      (node (ref "U29") (pin "3") (pinfunction "GND_3") (pintype "passive"))
      (node (ref "U3") (pin "3") (pinfunction "GND_3") (pintype "passive"))
      (node (ref "U30") (pin "3") (pinfunction "GND_3") (pintype "passive"))
      (node (ref "U31") (pin "3") (pinfunction "GND_3") (pintype "passive"))
      (node (ref "U32") (pin "3") (pinfunction "GND_3") (pintype "passive"))
      (node (ref "U33") (pin "3") (pinfunction "GND_3") (pintype "passive"))
      (node (ref "U34") (pin "3") (pinfunction "GND_3") (pintype "passive"))
      (node (ref "U35") (pin "3") (pinfunction "GND_3") (pintype "passive"))
      (node (ref "U4") (pin "3") (pinfunction "GND_3") (pintype "passive"))
      (node (ref "U5") (pin "3") (pinfunction "GND_3") (pintype "passive"))
      (node (ref "U6") (pin "3") (pinfunction "GND_3") (pintype "passive"))
      (node (ref "U7") (pin "3") (pinfunction "GND_3") (pintype "passive"))
      (node (ref "U8") (pin "3") (pinfunction "GND_3") (pintype "passive"))
      (node (ref "U9") (pin "3") (pinfunction "GND_3") (pintype "passive"))
    )
    (net (code "9") (name "Net-(U1-DOUT)") (class "Default")
      (node (ref "U1") (pin "2") (pinfunction "DOUT_2") (pintype "output"))
      (node (ref "U2") (pin "4") (pinfunction "DIN_4") (pintype "input"))
    )
    (net (code "10") (name "Net-(U2-DOUT)") (class "Default")
      (node (ref "U2") (pin "2") (pinfunction "DOUT_2") (pintype "output"))
      (node (ref "U3") (pin "4") (pinfunction "DIN_4") (pintype "input"))
    )
    (net (code "11") (name "Net-(U3-DOUT)") (class "Default")
      (node (ref "U3") (pin "2") (pinfunction "DOUT_2") (pintype "output"))
      (node (ref "U4") (pin "4") (pinfunction "DIN_4") (pintype "input"))
    )
    (net (code "12") (name "Net-(U4-DOUT)") (class "Default")
      (node (ref "U4") (pin "2") (pinfunction "DOUT_2") (pintype "output"))
      (node (ref "U5") (pin "4") (pinfunction "DIN_4") (pintype "input"))
    )
    (net (code "13") (name "Net-(U5-DOUT)") (class "Default")
      (node (ref "U5") (pin "2") (pinfunction "DOUT_2") (pintype "output"))
      (node (ref "U6") (pin "4") (pinfunction "DIN_4") (pintype "input"))
    )
    (net (code "14") (name "Net-(U6-DOUT)") (class "Default")
      (node (ref "U6") (pin "2") (pinfunction "DOUT_2") (pintype "output"))
      (node (ref "U7") (pin "4") (pinfunction "DIN_4") (pintype "input"))
    )
    (net (code "15") (name "Net-(U8-DOUT)") (class "Default")
      (node (ref "U8") (pin "2") (pinfunction "DOUT_2") (pintype "output"))
      (node (ref "U9") (pin "4") (pinfunction "DIN_4") (pintype "input"))
    )
    (net (code "16") (name "Net-(U10-DIN)") (class "Default")
      (node (ref "U10") (pin "4") (pinfunction "DIN_4") (pintype "input"))
      (node (ref "U9") (pin "2") (pinfunction "DOUT_2") (pintype "output"))
    )
    (net (code "17") (name "Net-(U10-DOUT)") (class "Default")
      (node (ref "U10") (pin "2") (pinfunction "DOUT_2") (pintype "output"))
      (node (ref "U11") (pin "4") (pinfunction "DIN_4") (pintype "input"))
    )
    (net (code "18") (name "Net-(U11-DOUT)") (class "Default")
      (node (ref "U11") (pin "2") (pinfunction "DOUT_2") (pintype "output"))
      (node (ref "U12") (pin "4") (pinfunction "DIN_4") (pintype "input"))
    )
    (net (code "19") (name "Net-(U12-DOUT)") (class "Default")
      (node (ref "U12") (pin "2") (pinfunction "DOUT_2") (pintype "output"))
      (node (ref "U13") (pin "4") (pinfunction "DIN_4") (pintype "input"))
    )
    (net (code "20") (name "Net-(U13-DOUT)") (class "Default")
      (node (ref "U13") (pin "2") (pinfunction "DOUT_2") (pintype "output"))
      (node (ref "U14") (pin "4") (pinfunction "DIN_4") (pintype "input"))
    )
    (net (code "21") (name "Net-(U15-DOUT)") (class "Default")
      (node (ref "U15") (pin "2") (pinfunction "DOUT_2") (pintype "output"))
      (node (ref "U16") (pin "4") (pinfunction "DIN_4") (pintype "input"))
    )
    (net (code "22") (name "Net-(U16-DOUT)") (class "Default")
      (node (ref "U16") (pin "2") (pinfunction "DOUT_2") (pintype "output"))
      (node (ref "U17") (pin "4") (pinfunction "DIN_4") (pintype "input"))
    )
    (net (code "23") (name "Net-(U17-DOUT)") (class "Default")
      (node (ref "U17") (pin "2") (pinfunction "DOUT_2") (pintype "output"))
      (node (ref "U18") (pin "4") (pinfunction "DIN_4") (pintype "input"))
    )
    (net (code "24") (name "Net-(U18-DOUT)") (class "Default")
      (node (ref "U18") (pin "2") (pinfunction "DOUT_2") (pintype "output"))
      (node (ref "U19") (pin "4") (pinfunction "DIN_4") (pintype "input"))
    )
    (net (code "25") (name "Net-(U19-DOUT)") (class "Default")
      (node (ref "U19") (pin "2") (pinfunction "DOUT_2") (pintype "output"))
      (node (ref "U20") (pin "4") (pinfunction "DIN_4") (pintype "input"))
    )
    (net (code "26") (name "Net-(U20-DOUT)") (class "Default")
      (node (ref "U20") (pin "2") (pinfunction "DOUT_2") (pintype "output"))
      (node (ref "U21") (pin "4") (pinfunction "DIN_4") (pintype "input"))
    )
    (net (code "27") (name "Net-(U22-DOUT)") (class "Default")
      (node (ref "U22") (pin "2") (pinfunction "DOUT_2") (pintype "output"))
      (node (ref "U23") (pin "4") (pinfunction "DIN_4") (pintype "input"))
    )
    (net (code "28") (name "Net-(U23-DOUT)") (class "Default")
      (node (ref "U23") (pin "2") (pinfunction "DOUT_2") (pintype "output"))
      (node (ref "U24") (pin "4") (pinfunction "DIN_4") (pintype "input"))
    )
    (net (code "29") (name "Net-(U24-DOUT)") (class "Default")
      (node (ref "U24") (pin "2") (pinfunction "DOUT_2") (pintype "output"))
      (node (ref "U25") (pin "4") (pinfunction "DIN_4") (pintype "input"))
    )
    (net (code "30") (name "Net-(U25-DOUT)") (class "Default")
      (node (ref "U25") (pin "2") (pinfunction "DOUT_2") (pintype "output"))
      (node (ref "U26") (pin "4") (pinfunction "DIN_4") (pintype "input"))
    )
    (net (code "31") (name "Net-(U26-DOUT)") (class "Default")
      (node (ref "U26") (pin "2") (pinfunction "DOUT_2") (pintype "output"))
      (node (ref "U27") (pin "4") (pinfunction "DIN_4") (pintype "input"))
    )
    (net (code "32") (name "Net-(U27-DOUT)") (class "Default")
      (node (ref "U27") (pin "2") (pinfunction "DOUT_2") (pintype "output"))
      (node (ref "U28") (pin "4") (pinfunction "DIN_4") (pintype "input"))
    )
    (net (code "33") (name "Net-(U29-DOUT)") (class "Default")
      (node (ref "U29") (pin "2") (pinfunction "DOUT_2") (pintype "output"))
      (node (ref "U30") (pin "4") (pinfunction "DIN_4") (pintype "input"))
    )
    (net (code "34") (name "Net-(U30-DOUT)") (class "Default")
      (node (ref "U30") (pin "2") (pinfunction "DOUT_2") (pintype "output"))
      (node (ref "U31") (pin "4") (pinfunction "DIN_4") (pintype "input"))
    )
    (net (code "35") (name "Net-(U31-DOUT)") (class "Default")
      (node (ref "U31") (pin "2") (pinfunction "DOUT_2") (pintype "output"))
      (node (ref "U32") (pin "4") (pinfunction "DIN_4") (pintype "input"))
    )
    (net (code "36") (name "Net-(U32-DOUT)") (class "Default")
      (node (ref "U32") (pin "2") (pinfunction "DOUT_2") (pintype "output"))
      (node (ref "U33") (pin "4") (pinfunction "DIN_4") (pintype "input"))
    )
    (net (code "37") (name "Net-(U33-DOUT)") (class "Default")
      (node (ref "U33") (pin "2") (pinfunction "DOUT_2") (pintype "output"))
      (node (ref "U34") (pin "4") (pinfunction "DIN_4") (pintype "input"))
    )
    (net (code "38") (name "Net-(U34-DOUT)") (class "Default")
      (node (ref "U34") (pin "2") (pinfunction "DOUT_2") (pintype "output"))
      (node (ref "U35") (pin "4") (pinfunction "DIN_4") (pintype "input"))
    )
  )
)
